# MotorBoard.net
KiCad netlist of a schematic drawn in Altium Designer
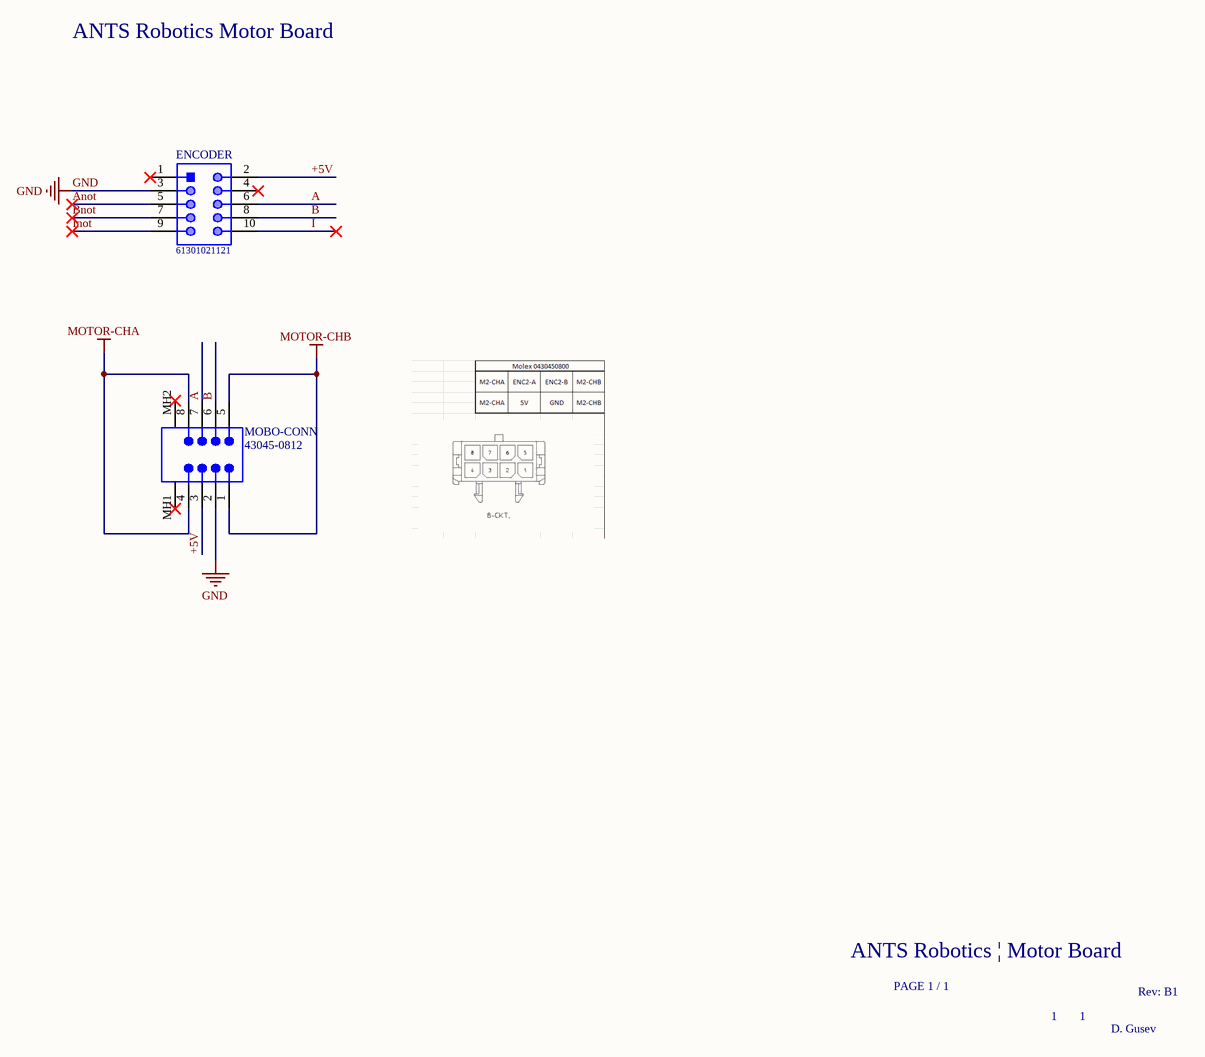
[diagram p0: MotorBoard.SchDoc]

(export (version "E")
  (design (tool "Eeschema 10.0.6"))
  (components
    (comp (ref "ENCODER")
      (value "61301021121")
      (footprint "61301021121")
      (description "THT Vertical Pin Header WR-PHD, Pitch 2.54 mm, Dual Row, 10 pins")
      (fields (field (name "MANUFACTURER") "Wurth Elektronik") (field (name "PUBLISHER") "WurthElektronik"))
      (libsource (lib "Altium Content Vault") (part "WE-CN-2P-M-R10"))
    )
    (comp (ref "MOBO-CONN")
      (value "43045-0812")
      (footprint "MOLX-43045-0812_V")
      (libsource (lib "Altium Content Vault") (part "MOLX-43045-0812"))
    )
  )
  (nets
    (net (code "1") (name "/+5V") (class "Default")
      (node (ref "ENCODER") (pin "2") (pinfunction "2_2") (pintype "passive"))
      (node (ref "MOBO-CONN") (pin "3") (pinfunction "3_3") (pintype "passive"))
    )
    (net (code "2") (name "/A") (class "Default")
      (node (ref "ENCODER") (pin "6") (pinfunction "6_6") (pintype "passive"))
      (node (ref "MOBO-CONN") (pin "7") (pinfunction "7_7") (pintype "passive"))
    )
    (net (code "3") (name "/Anot") (class "Default")
      (node (ref "ENCODER") (pin "5") (pinfunction "5_5") (pintype "passive+no_connect"))
    )
    (net (code "4") (name "/B") (class "Default")
      (node (ref "ENCODER") (pin "8") (pinfunction "8_8") (pintype "passive"))
      (node (ref "MOBO-CONN") (pin "6") (pinfunction "6_6") (pintype "passive"))
    )
    (net (code "5") (name "/Bnot") (class "Default")
      (node (ref "ENCODER") (pin "7") (pinfunction "7_7") (pintype "passive+no_connect"))
    )
    (net (code "6") (name "/I") (class "Default")
      (node (ref "ENCODER") (pin "10") (pinfunction "10_10") (pintype "passive+no_connect"))
    )
    (net (code "7") (name "/Inot") (class "Default")
      (node (ref "ENCODER") (pin "9") (pinfunction "9_9") (pintype "passive+no_connect"))
    )
    (net (code "8") (name "GND") (class "Default")
      (node (ref "ENCODER") (pin "3") (pinfunction "3_3") (pintype "passive"))
      (node (ref "MOBO-CONN") (pin "2") (pinfunction "2_2") (pintype "passive"))
    )
    (net (code "9") (name "MOTOR-CHA") (class "Default")
      (node (ref "MOBO-CONN") (pin "4") (pinfunction "4_4") (pintype "passive"))
      (node (ref "MOBO-CONN") (pin "8") (pinfunction "8_8") (pintype "passive"))
    )
    (net (code "10") (name "MOTOR-CHB") (class "Default")
      (node (ref "MOBO-CONN") (pin "1") (pinfunction "1_1") (pintype "passive"))
      (node (ref "MOBO-CONN") (pin "5") (pinfunction "5_5") (pintype "passive"))
    )
    (net (code "11") (name "unconnected-(ENCODER-Pad1)") (class "Default")
      (node (ref "ENCODER") (pin "1") (pinfunction "1_1") (pintype "passive+no_connect"))
    )
    (net (code "12") (name "unconnected-(ENCODER-Pad4)") (class "Default")
      (node (ref "ENCODER") (pin "4") (pinfunction "4_4") (pintype "passive+no_connect"))
    )
    (net (code "13") (name "unconnected-(MOBO-CONN-PadMH1)") (class "Default")
      (node (ref "MOBO-CONN") (pin "MH1") (pinfunction "MH1_MH1") (pintype "passive+no_connect"))
    )
    (net (code "14") (name "unconnected-(MOBO-CONN-PadMH2)") (class "Default")
      (node (ref "MOBO-CONN") (pin "MH2") (pinfunction "MH2_MH2") (pintype "passive+no_connect"))
    )
  )
)
